# SCH_PCB-Card_2025-01-08.net
KiCad netlist of a schematic drawn in EasyEDA
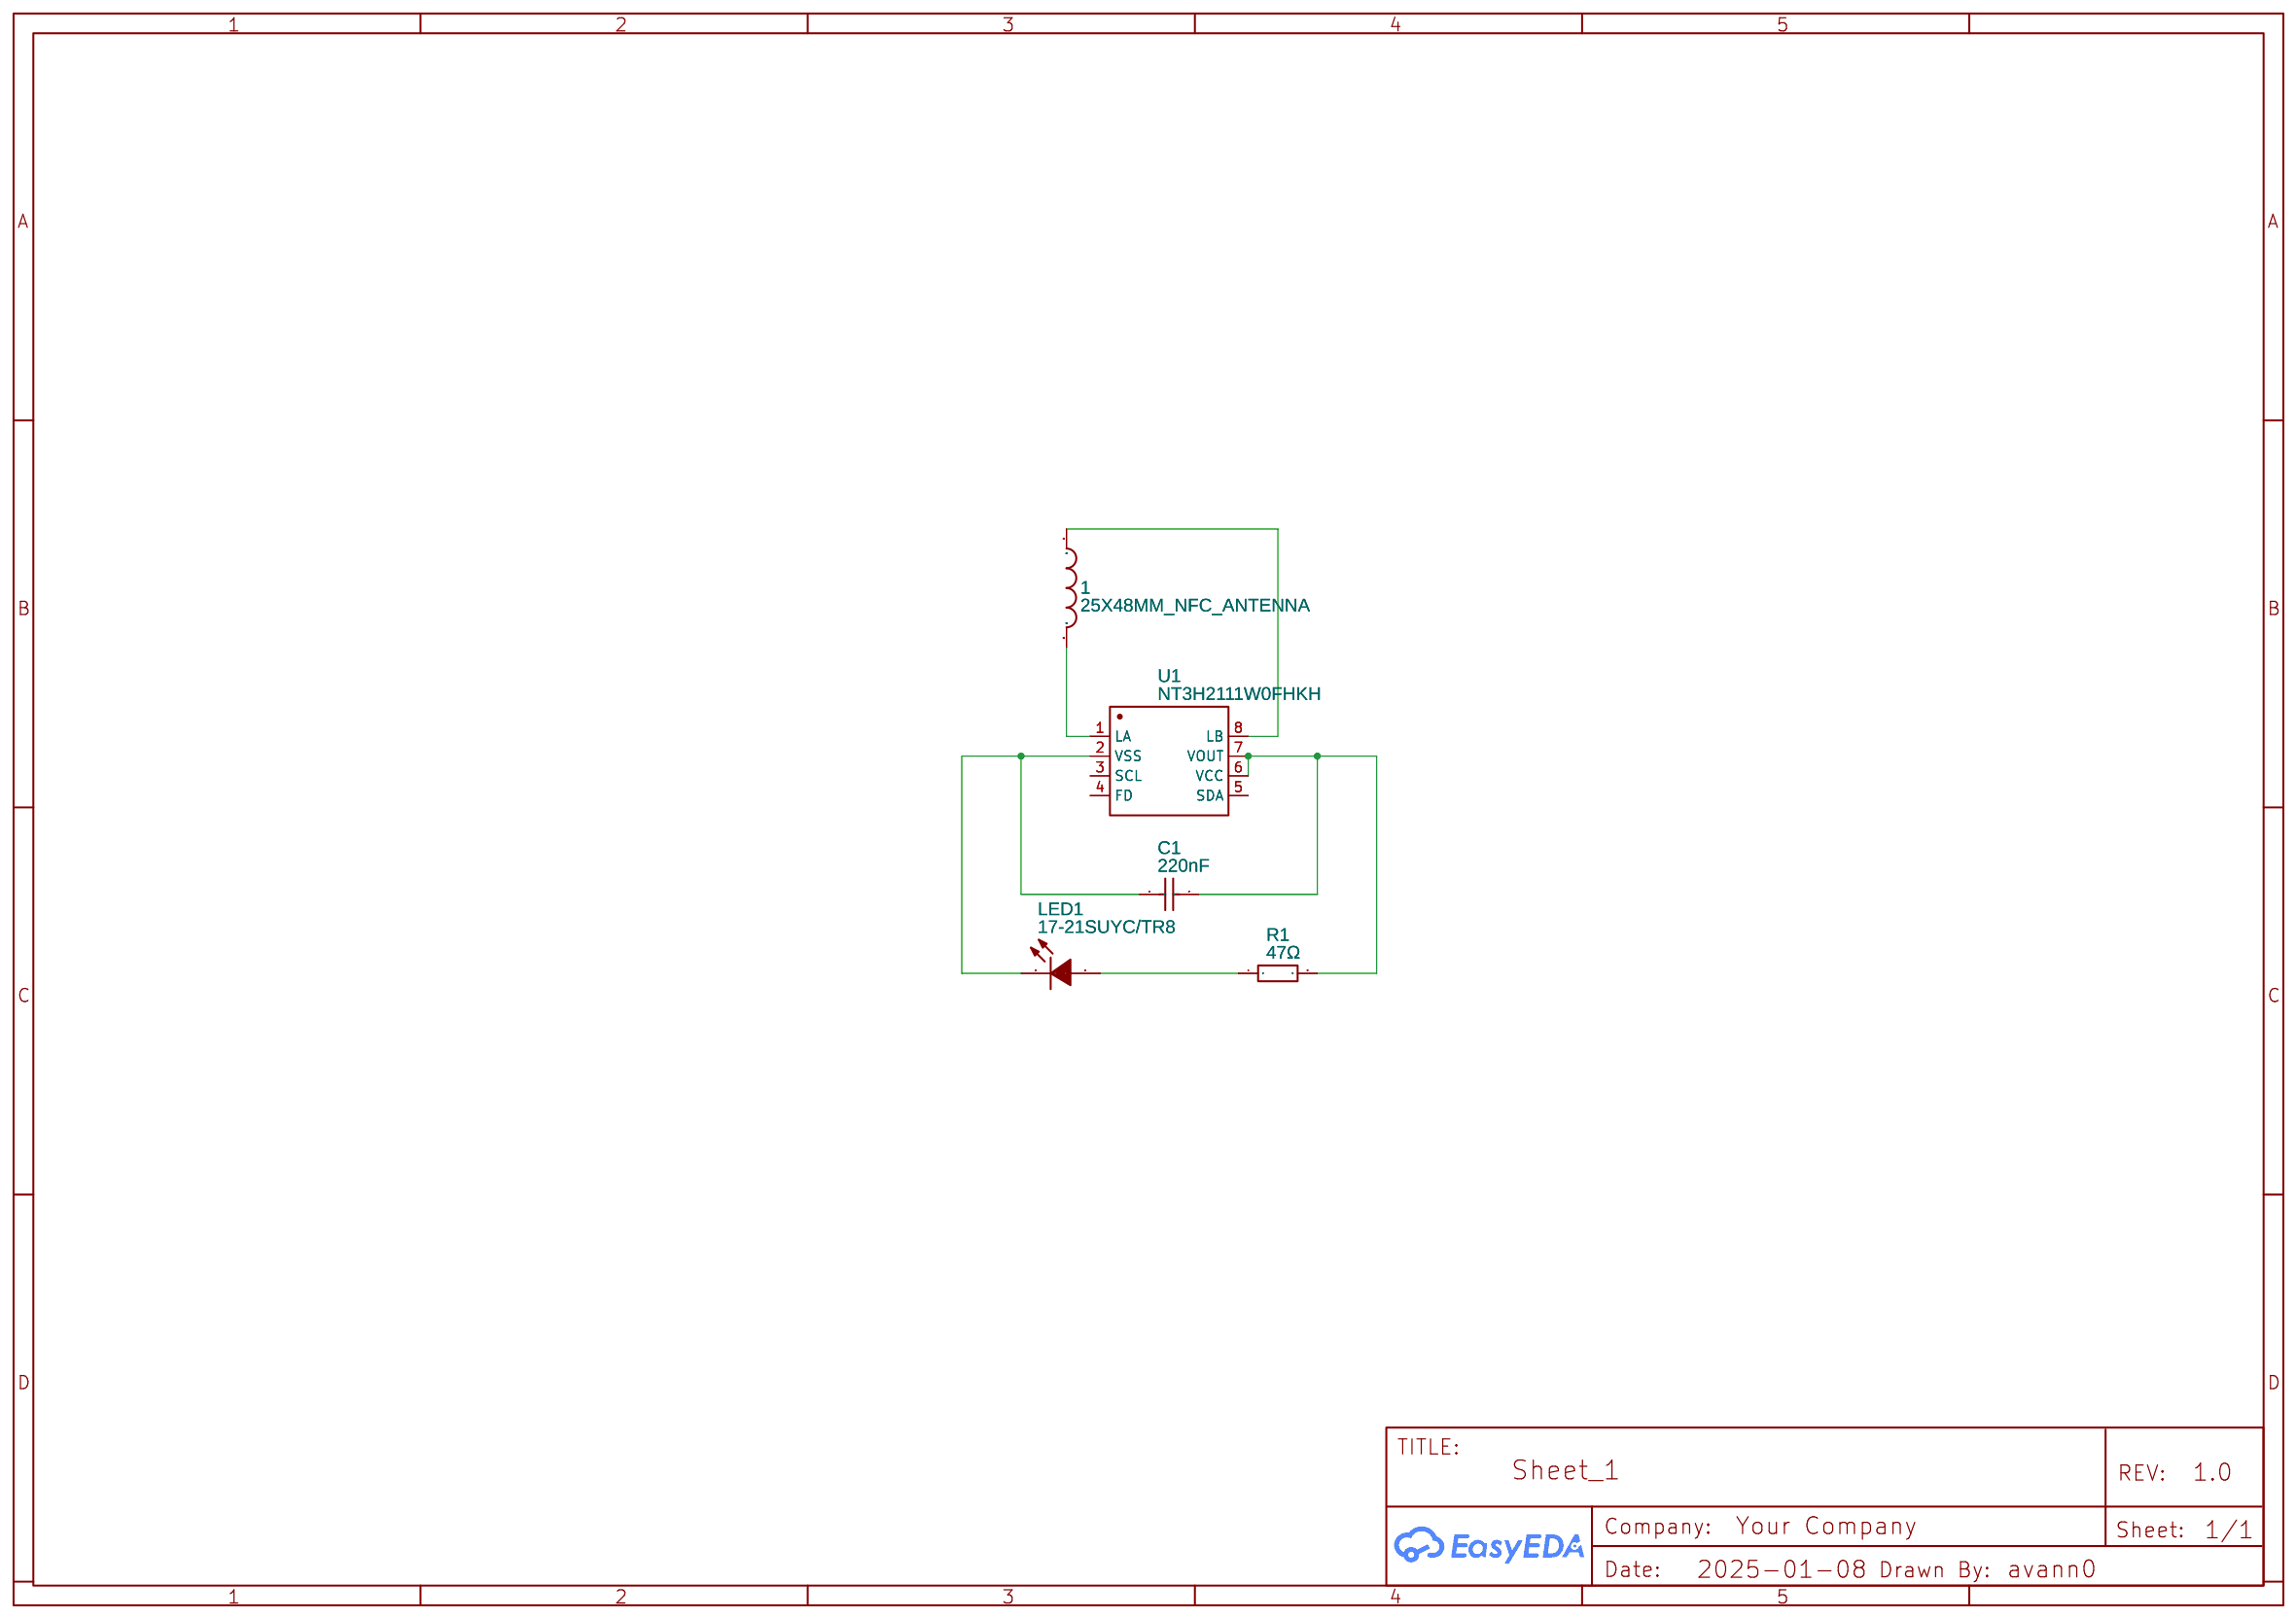
[diagram p0: schematic sheet]

(export (version "E")
  (design (tool "Eeschema 10.0.6"))
  (components
    (comp (ref "1") (value "25X48MM_NFC_ANTENNA") (libsource (lib "") (part "25X48MM_NFC_ANTENNA")))
    (comp (ref "C1")
      (value "220nF")
      (fields
        (field (name "Manufacturer Part") "CL10B224KA8NNNC")
        (field (name "Manufacturer") "SAMSUNG(三星)")
      )
      (libsource (lib "") (part "CL10B224KA8NNNC"))
    )
    (comp (ref "LED1")
      (value "17-21SUYC/TR8")
      (fields (field (name "Manufacturer Part") "KT-0805黄灯") (field (name "Manufacturer") "KENTO"))
      (libsource (lib "") (part "17-21SUYC/TR8"))
    )
    (comp (ref "R1")
      (value "47Ω")
      (fields
        (field (name "Manufacturer Part") "0603WAF470JT5E")
        (field (name "Manufacturer") "UNI-ROYAL(厚声)")
      )
      (libsource (lib "") (part "0603WAF470JT5E"))
    )
    (comp (ref "U1")
      (value "NT3H2111W0FHKH")
      (fields (field (name "Manufacturer") "NXP(恩智浦)"))
      (libsource (lib "") (part "NT3H2111W0FHKH"))
    )
  )
  (nets
    (net (code "1") (name "Net-(LED1-+)") (class "Default")
      (node (ref "LED1") (pin "1") (pinfunction "+_1") (pintype "unspecified"))
      (node (ref "R1") (pin "1") (pinfunction "1_1") (pintype "input"))
    )
    (net (code "2") (name "Net-(LED1--)") (class "Default")
      (node (ref "C1") (pin "1") (pinfunction "1_1") (pintype "input"))
      (node (ref "LED1") (pin "2") (pinfunction "-_2") (pintype "unspecified"))
      (node (ref "U1") (pin "2") (pinfunction "VSS_2") (pintype "unspecified"))
    )
    (net (code "3") (name "Net-(U1-LA)") (class "Default")
      (node (ref "1") (pin "P$2") (pinfunction "P$2_P$2") (pintype "bidirectional"))
      (node (ref "U1") (pin "1") (pinfunction "LA_1") (pintype "unspecified"))
    )
    (net (code "4") (name "Net-(U1-LB)") (class "Default")
      (node (ref "1") (pin "P$1") (pinfunction "P$1_P$1") (pintype "bidirectional"))
      (node (ref "U1") (pin "8") (pinfunction "LB_8") (pintype "unspecified"))
    )
    (net (code "5") (name "Net-(U1-VCC)") (class "Default")
      (node (ref "C1") (pin "2") (pinfunction "2_2") (pintype "input"))
      (node (ref "R1") (pin "2") (pinfunction "2_2") (pintype "input"))
      (node (ref "U1") (pin "6") (pinfunction "VCC_6") (pintype "unspecified"))
      (node (ref "U1") (pin "7") (pinfunction "VOUT_7") (pintype "unspecified"))
    )
    (net (code "6") (name "unconnected-(U1-FD-Pad4)") (class "Default")
      (node (ref "U1") (pin "4") (pinfunction "FD_4") (pintype "unspecified"))
    )
    (net (code "7") (name "unconnected-(U1-SCL-Pad3)") (class "Default")
      (node (ref "U1") (pin "3") (pinfunction "SCL_3") (pintype "unspecified"))
    )
    (net (code "8") (name "unconnected-(U1-SDA-Pad5)") (class "Default")
      (node (ref "U1") (pin "5") (pinfunction "SDA_5") (pintype "unspecified"))
    )
  )
)
